# Driver_Fet.net
KiCad netlist of a schematic drawn in Altium Designer
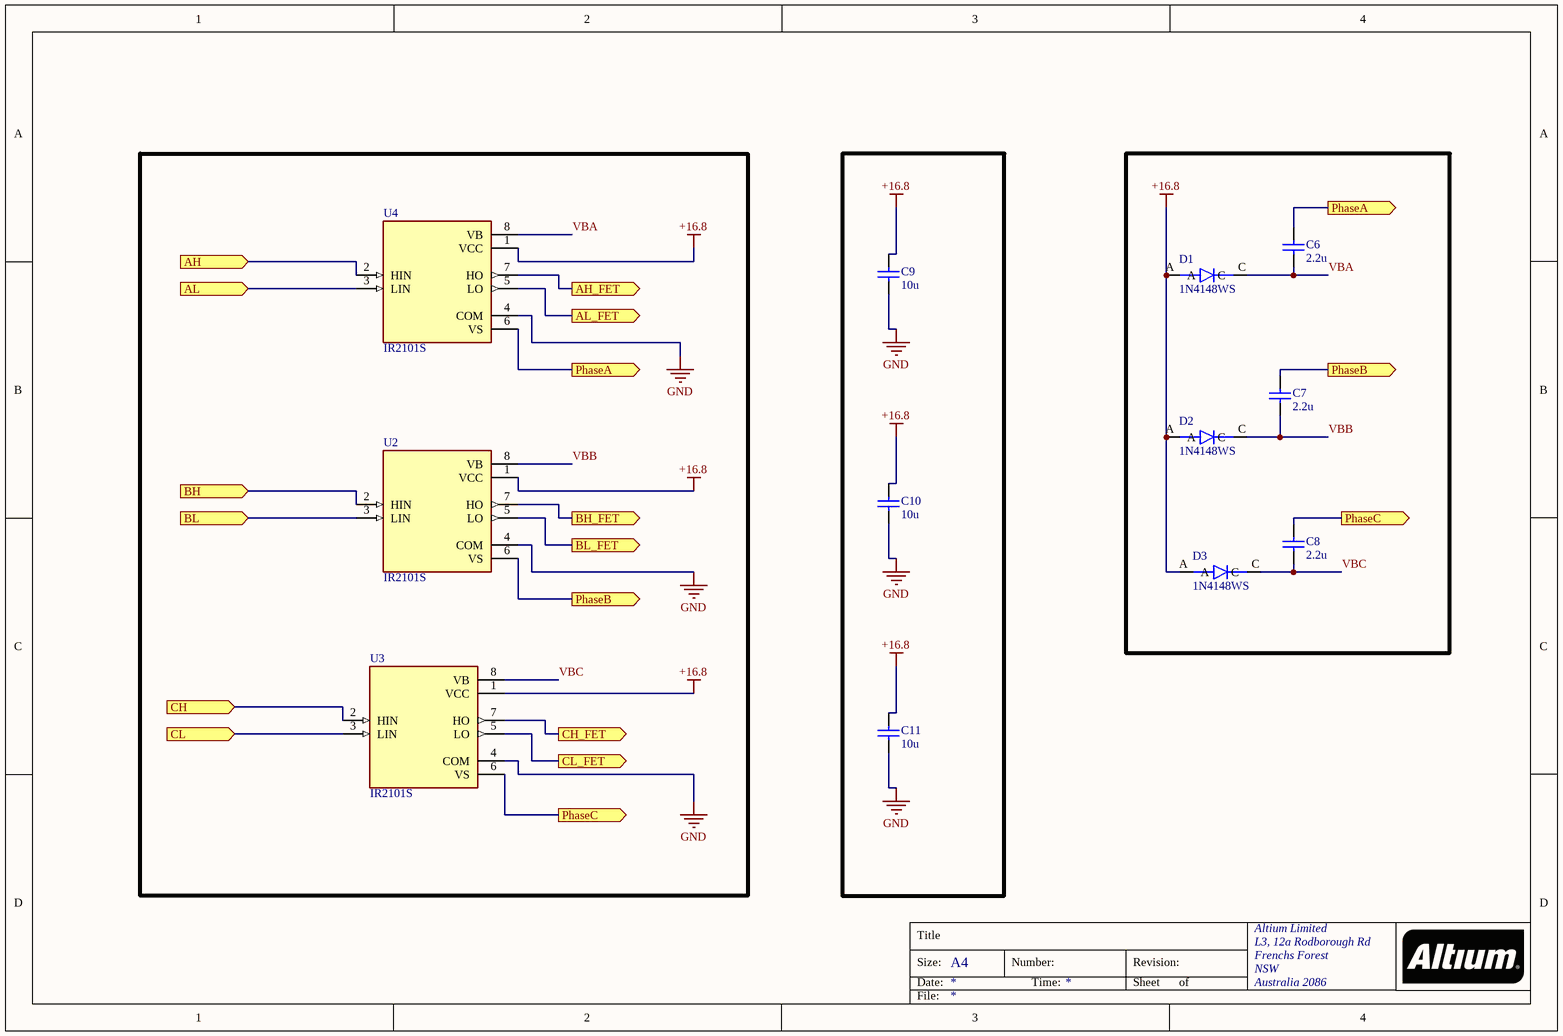
[diagram p0: Driver_Fet.SchDoc]

(export (version "E")
  (design (tool "Eeschema 10.0.6"))
  (components
    (comp (ref "C6")
      (value "2.2u")
      (footprint "tu 0805")
      (description "Dán")
      (libsource (lib "Tu dien") (part "Tu 0805 106 16V 10%"))
    )
    (comp (ref "C7")
      (value "2.2u")
      (footprint "tu 0805")
      (description "Dán")
      (libsource (lib "Tu dien") (part "Tu 0805 106 16V 10%"))
    )
    (comp (ref "C8")
      (value "2.2u")
      (footprint "tu 0805")
      (description "Dán")
      (libsource (lib "Tu dien") (part "Tu 0805 106 16V 10%"))
    )
    (comp (ref "C9")
      (value "10u")
      (footprint "tu 0805")
      (description "Dán")
      (libsource (lib "Tu dien") (part "Tu 0805 106 16V 10%"))
    )
    (comp (ref "C10")
      (value "10u")
      (footprint "tu 0805")
      (description "Dán")
      (libsource (lib "Tu dien") (part "Tu 0805 106 16V 10%"))
    )
    (comp (ref "C11")
      (value "10u")
      (footprint "tu 0805")
      (description "Dán")
      (libsource (lib "Tu dien") (part "Tu 0805 106 16V 10%"))
    )
    (comp (ref "D1")
      (value "1N4148WS")
      (footprint "SODFL2512X100N")
      (description "Diode Standard 75V 300mA (DC) Surface Mount SOD-323")
      (fields (field (name "MF") "ON Semiconductor"))
      (libsource (lib "1N4148WS") (part "1N4148WS"))
    )
    (comp (ref "D2")
      (value "1N4148WS")
      (footprint "SODFL2512X100N")
      (description "Diode Standard 75V 300mA (DC) Surface Mount SOD-323")
      (fields (field (name "MF") "ON Semiconductor"))
      (libsource (lib "1N4148WS") (part "1N4148WS"))
    )
    (comp (ref "D3")
      (value "1N4148WS")
      (footprint "SODFL2512X100N")
      (description "Diode Standard 75V 300mA (DC) Surface Mount SOD-323")
      (fields (field (name "MF") "ON Semiconductor"))
      (libsource (lib "1N4148WS") (part "1N4148WS"))
    )
    (comp (ref "U2")
      (value "IR2101S")
      (footprint "SOIC127P600X175-8N")
      (description "Half-Bridge Gate Driver IC Non-Inverting 8-SOIC")
      (fields (field (name "MF") "Infineon Technologies"))
      (libsource (lib "IR2101S") (part "IR2101S"))
    )
    (comp (ref "U3")
      (value "IR2101S")
      (footprint "SOIC127P600X175-8N")
      (description "Half-Bridge Gate Driver IC Non-Inverting 8-SOIC")
      (fields (field (name "MF") "Infineon Technologies"))
      (libsource (lib "IR2101S") (part "IR2101S"))
    )
    (comp (ref "U4")
      (value "IR2101S")
      (footprint "SOIC127P600X175-8N")
      (description "Half-Bridge Gate Driver IC Non-Inverting 8-SOIC")
      (fields (field (name "MF") "Infineon Technologies"))
      (libsource (lib "IR2101S") (part "IR2101S"))
    )
  )
  (nets
    (net (code "1") (name "+16.8") (class "Default")
      (node (ref "C10") (pin "1") (pinfunction "1_1") (pintype "passive"))
      (node (ref "C11") (pin "1") (pinfunction "1_1") (pintype "passive"))
      (node (ref "C9") (pin "1") (pinfunction "1_1") (pintype "passive"))
      (node (ref "D1") (pin "A") (pinfunction "A_A") (pintype "passive"))
      (node (ref "D2") (pin "A") (pinfunction "A_A") (pintype "passive"))
      (node (ref "D3") (pin "A") (pinfunction "A_A") (pintype "passive"))
      (node (ref "U2") (pin "1") (pinfunction "VCC_1") (pintype "power_in"))
      (node (ref "U3") (pin "1") (pinfunction "VCC_1") (pintype "power_in"))
      (node (ref "U4") (pin "1") (pinfunction "VCC_1") (pintype "power_in"))
    )
    (net (code "2") (name "/AH") (class "Default")
      (node (ref "U4") (pin "2") (pinfunction "HIN_2") (pintype "input"))
    )
    (net (code "3") (name "/AH_FET") (class "Default")
      (node (ref "U4") (pin "7") (pinfunction "HO_7") (pintype "output"))
    )
    (net (code "4") (name "/AL") (class "Default")
      (node (ref "U4") (pin "3") (pinfunction "LIN_3") (pintype "input"))
    )
    (net (code "5") (name "/AL_FET") (class "Default")
      (node (ref "U4") (pin "5") (pinfunction "LO_5") (pintype "output"))
    )
    (net (code "6") (name "/BH") (class "Default")
      (node (ref "U2") (pin "2") (pinfunction "HIN_2") (pintype "input"))
    )
    (net (code "7") (name "/BH_FET") (class "Default")
      (node (ref "U2") (pin "7") (pinfunction "HO_7") (pintype "output"))
    )
    (net (code "8") (name "/BL") (class "Default")
      (node (ref "U2") (pin "3") (pinfunction "LIN_3") (pintype "input"))
    )
    (net (code "9") (name "/BL_FET") (class "Default")
      (node (ref "U2") (pin "5") (pinfunction "LO_5") (pintype "output"))
    )
    (net (code "10") (name "/CH") (class "Default")
      (node (ref "U3") (pin "2") (pinfunction "HIN_2") (pintype "input"))
    )
    (net (code "11") (name "/CH_FET") (class "Default")
      (node (ref "U3") (pin "7") (pinfunction "HO_7") (pintype "output"))
    )
    (net (code "12") (name "/CL") (class "Default")
      (node (ref "U3") (pin "3") (pinfunction "LIN_3") (pintype "input"))
    )
    (net (code "13") (name "/CL_FET") (class "Default")
      (node (ref "U3") (pin "5") (pinfunction "LO_5") (pintype "output"))
    )
    (net (code "14") (name "/PhaseA") (class "Default")
      (node (ref "C6") (pin "1") (pinfunction "1_1") (pintype "passive"))
      (node (ref "U4") (pin "6") (pinfunction "VS_6") (pintype "passive"))
    )
    (net (code "15") (name "/PhaseB") (class "Default")
      (node (ref "C7") (pin "1") (pinfunction "1_1") (pintype "passive"))
      (node (ref "U2") (pin "6") (pinfunction "VS_6") (pintype "passive"))
    )
    (net (code "16") (name "/PhaseC") (class "Default")
      (node (ref "C8") (pin "1") (pinfunction "1_1") (pintype "passive"))
      (node (ref "U3") (pin "6") (pinfunction "VS_6") (pintype "passive"))
    )
    (net (code "17") (name "/VBA") (class "Default")
      (node (ref "C6") (pin "2") (pinfunction "2_2") (pintype "passive"))
      (node (ref "D1") (pin "C") (pinfunction "C_C") (pintype "passive"))
      (node (ref "U4") (pin "8") (pinfunction "VB_8") (pintype "passive"))
    )
    (net (code "18") (name "/VBB") (class "Default")
      (node (ref "C7") (pin "2") (pinfunction "2_2") (pintype "passive"))
      (node (ref "D2") (pin "C") (pinfunction "C_C") (pintype "passive"))
      (node (ref "U2") (pin "8") (pinfunction "VB_8") (pintype "passive"))
    )
    (net (code "19") (name "/VBC") (class "Default")
      (node (ref "C8") (pin "2") (pinfunction "2_2") (pintype "passive"))
      (node (ref "D3") (pin "C") (pinfunction "C_C") (pintype "passive"))
      (node (ref "U3") (pin "8") (pinfunction "VB_8") (pintype "passive"))
    )
    (net (code "20") (name "GND") (class "Default")
      (node (ref "C10") (pin "2") (pinfunction "2_2") (pintype "passive"))
      (node (ref "C11") (pin "2") (pinfunction "2_2") (pintype "passive"))
      (node (ref "C9") (pin "2") (pinfunction "2_2") (pintype "passive"))
      (node (ref "U2") (pin "4") (pinfunction "COM_4") (pintype "power_in"))
      (node (ref "U3") (pin "4") (pinfunction "COM_4") (pintype "power_in"))
      (node (ref "U4") (pin "4") (pinfunction "COM_4") (pintype "power_in"))
    )
  )
)
